# SIDEPANELV5.net
KiCad netlist of a schematic drawn in EAGLE
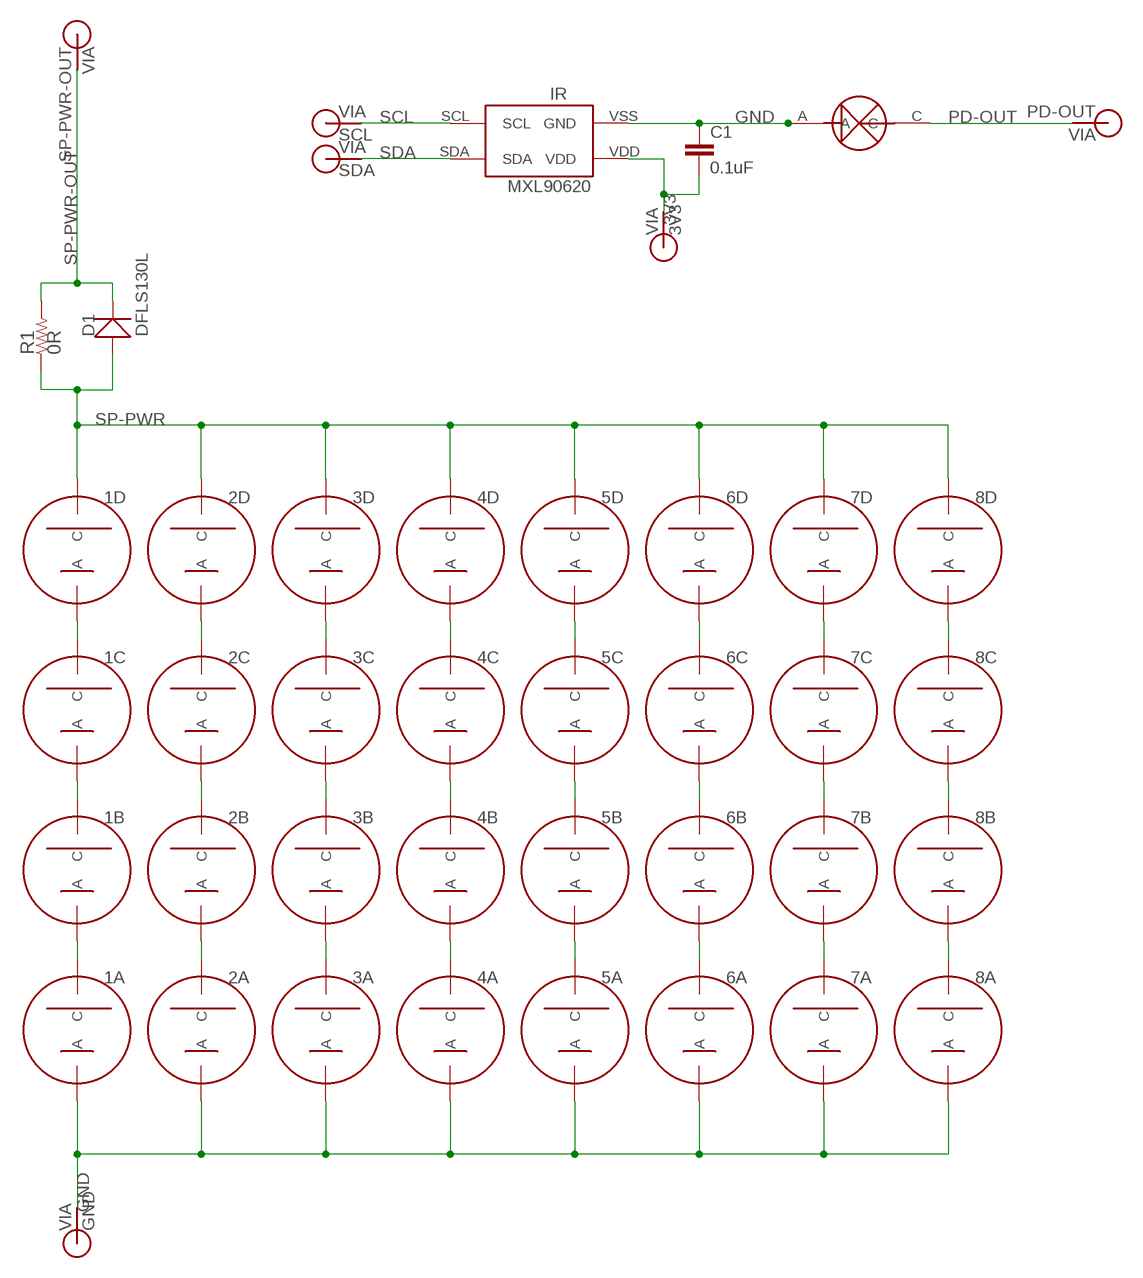
[diagram p0: schematic, sheet 1]

(export (version "E")
  (design (tool "Eeschema 10.0.6"))
  (components
    (comp (ref "1A")
      (value "SOLARCELLV3")
      (footprint "eagle-import:TRISOLX-V3")
      (libsource (lib "eagle-import") (part "SOLARCELLV3"))
    )
    (comp (ref "1B")
      (value "SOLARCELLV3")
      (footprint "eagle-import:TRISOLX-V3")
      (libsource (lib "eagle-import") (part "SOLARCELLV3"))
    )
    (comp (ref "1C")
      (value "SOLARCELLV3")
      (footprint "eagle-import:TRISOLX-V3")
      (libsource (lib "eagle-import") (part "SOLARCELLV3"))
    )
    (comp (ref "1D")
      (value "SOLARCELLV3")
      (footprint "eagle-import:TRISOLX-V3")
      (libsource (lib "eagle-import") (part "SOLARCELLV3"))
    )
    (comp (ref "2A")
      (value "SOLARCELLV3")
      (footprint "eagle-import:TRISOLX-V3")
      (libsource (lib "eagle-import") (part "SOLARCELLV3"))
    )
    (comp (ref "2B")
      (value "SOLARCELLV3")
      (footprint "eagle-import:TRISOLX-V3")
      (libsource (lib "eagle-import") (part "SOLARCELLV3"))
    )
    (comp (ref "2C")
      (value "SOLARCELLV3")
      (footprint "eagle-import:TRISOLX-V3")
      (libsource (lib "eagle-import") (part "SOLARCELLV3"))
    )
    (comp (ref "2D")
      (value "SOLARCELLV3")
      (footprint "eagle-import:TRISOLX-V3")
      (libsource (lib "eagle-import") (part "SOLARCELLV3"))
    )
    (comp (ref "3A")
      (value "SOLARCELLV3")
      (footprint "eagle-import:TRISOLX-V3")
      (libsource (lib "eagle-import") (part "SOLARCELLV3"))
    )
    (comp (ref "3B")
      (value "SOLARCELLV3")
      (footprint "eagle-import:TRISOLX-V3")
      (libsource (lib "eagle-import") (part "SOLARCELLV3"))
    )
    (comp (ref "3C")
      (value "SOLARCELLV3")
      (footprint "eagle-import:TRISOLX-V3")
      (libsource (lib "eagle-import") (part "SOLARCELLV3"))
    )
    (comp (ref "3D")
      (value "SOLARCELLV3")
      (footprint "eagle-import:TRISOLX-V3")
      (libsource (lib "eagle-import") (part "SOLARCELLV3"))
    )
    (comp (ref "3V3")
      (value "3V3")
      (footprint "eagle-import:VIA-60MIL")
      (libsource (lib "eagle-import") (part "VIA-60MIL"))
    )
    (comp (ref "4A")
      (value "SOLARCELLV3")
      (footprint "eagle-import:TRISOLX-V3")
      (libsource (lib "eagle-import") (part "SOLARCELLV3"))
    )
    (comp (ref "4B")
      (value "SOLARCELLV3")
      (footprint "eagle-import:TRISOLX-V3")
      (libsource (lib "eagle-import") (part "SOLARCELLV3"))
    )
    (comp (ref "4C")
      (value "SOLARCELLV3")
      (footprint "eagle-import:TRISOLX-V3")
      (libsource (lib "eagle-import") (part "SOLARCELLV3"))
    )
    (comp (ref "4D")
      (value "SOLARCELLV3")
      (footprint "eagle-import:TRISOLX-V3")
      (libsource (lib "eagle-import") (part "SOLARCELLV3"))
    )
    (comp (ref "5A")
      (value "SOLARCELLV3")
      (footprint "eagle-import:TRISOLX-V3")
      (libsource (lib "eagle-import") (part "SOLARCELLV3"))
    )
    (comp (ref "5B")
      (value "SOLARCELLV3")
      (footprint "eagle-import:TRISOLX-V3")
      (libsource (lib "eagle-import") (part "SOLARCELLV3"))
    )
    (comp (ref "5C")
      (value "SOLARCELLV3")
      (footprint "eagle-import:TRISOLX-V3")
      (libsource (lib "eagle-import") (part "SOLARCELLV3"))
    )
    (comp (ref "5D")
      (value "SOLARCELLV3")
      (footprint "eagle-import:TRISOLX-V3")
      (libsource (lib "eagle-import") (part "SOLARCELLV3"))
    )
    (comp (ref "6A")
      (value "SOLARCELLV3")
      (footprint "eagle-import:TRISOLX-V3")
      (libsource (lib "eagle-import") (part "SOLARCELLV3"))
    )
    (comp (ref "6B")
      (value "SOLARCELLV3")
      (footprint "eagle-import:TRISOLX-V3")
      (libsource (lib "eagle-import") (part "SOLARCELLV3"))
    )
    (comp (ref "6C")
      (value "SOLARCELLV3")
      (footprint "eagle-import:TRISOLX-V3")
      (libsource (lib "eagle-import") (part "SOLARCELLV3"))
    )
    (comp (ref "6D")
      (value "SOLARCELLV3")
      (footprint "eagle-import:TRISOLX-V3")
      (libsource (lib "eagle-import") (part "SOLARCELLV3"))
    )
    (comp (ref "7A")
      (value "SOLARCELLV3")
      (footprint "eagle-import:TRISOLX-V3")
      (libsource (lib "eagle-import") (part "SOLARCELLV3"))
    )
    (comp (ref "7B")
      (value "SOLARCELLV3")
      (footprint "eagle-import:TRISOLX-V3")
      (libsource (lib "eagle-import") (part "SOLARCELLV3"))
    )
    (comp (ref "7C")
      (value "SOLARCELLV3")
      (footprint "eagle-import:TRISOLX-V3")
      (libsource (lib "eagle-import") (part "SOLARCELLV3"))
    )
    (comp (ref "7D")
      (value "SOLARCELLV3")
      (footprint "eagle-import:TRISOLX-V3")
      (libsource (lib "eagle-import") (part "SOLARCELLV3"))
    )
    (comp (ref "8A")
      (value "SOLARCELLV3")
      (footprint "eagle-import:TRISOLX-V3")
      (libsource (lib "eagle-import") (part "SOLARCELLV3"))
    )
    (comp (ref "8B")
      (value "SOLARCELLV3")
      (footprint "eagle-import:TRISOLX-V3")
      (libsource (lib "eagle-import") (part "SOLARCELLV3"))
    )
    (comp (ref "8C")
      (value "SOLARCELLV3")
      (footprint "eagle-import:TRISOLX-V3")
      (libsource (lib "eagle-import") (part "SOLARCELLV3"))
    )
    (comp (ref "8D")
      (value "SOLARCELLV3")
      (footprint "eagle-import:TRISOLX-V3")
      (libsource (lib "eagle-import") (part "SOLARCELLV3"))
    )
    (comp (ref "C1")
      (value "0.1uF")
      (footprint "eagle-import:0805")
      (libsource (lib "eagle-import") (part "CAP0805"))
    )
    (comp (ref "D1")
      (value "DFLS130L")
      (footprint "eagle-import:PWRDI-123")
      (libsource (lib "eagle-import") (part "DFLS130L"))
    )
    (comp (ref "GND")
      (value "GND")
      (footprint "eagle-import:VIA-60MIL")
      (libsource (lib "eagle-import") (part "VIA-60MIL"))
    )
    (comp (ref "IR")
      (value "MXL90620")
      (footprint "eagle-import:MXL90620")
      (libsource (lib "eagle-import") (part "MXL90620"))
    )
    (comp (ref "PD")
      (value "PHOTODETECTOR")
      (footprint "eagle-import:PHOTODECTORDEVICE2")
      (libsource (lib "eagle-import") (part "PHOTODETECTOR"))
    )
    (comp (ref "PD-OUT")
      (value "PD-OUT")
      (footprint "eagle-import:VIA-60MIL")
      (libsource (lib "eagle-import") (part "VIA-60MIL"))
    )
    (comp (ref "PWR-OUT")
      (value "SP-PWR-OUT")
      (footprint "eagle-import:VIA-60MIL")
      (libsource (lib "eagle-import") (part "VIA-60MIL"))
    )
    (comp (ref "R1")
      (value "0R")
      (footprint "eagle-import:1210")
      (libsource (lib "eagle-import") (part "RES1210"))
    )
    (comp (ref "SCL")
      (value "SCL")
      (footprint "eagle-import:VIA-60MIL")
      (libsource (lib "eagle-import") (part "VIA-60MIL"))
    )
    (comp (ref "SDA")
      (value "SDA")
      (footprint "eagle-import:VIA-60MIL")
      (libsource (lib "eagle-import") (part "VIA-60MIL"))
    )
  )
  (nets
    (net (code "1") (name "/3V3") (class "Default")
      (node (ref "3V3") (pin "P$1") (pinfunction "P$1_P$1") (pintype "bidirectional"))
      (node (ref "C1") (pin "2") (pinfunction "2_2") (pintype "passive"))
      (node (ref "IR") (pin "VDD") (pinfunction "VDD_VDD") (pintype "bidirectional"))
    )
    (net (code "2") (name "/GND") (class "Default")
      (node (ref "1A") (pin "ANODE") (pinfunction "A_ANODE") (pintype "bidirectional"))
      (node (ref "2A") (pin "ANODE") (pinfunction "A_ANODE") (pintype "bidirectional"))
      (node (ref "3A") (pin "ANODE") (pinfunction "A_ANODE") (pintype "bidirectional"))
      (node (ref "4A") (pin "ANODE") (pinfunction "A_ANODE") (pintype "bidirectional"))
      (node (ref "5A") (pin "ANODE") (pinfunction "A_ANODE") (pintype "bidirectional"))
      (node (ref "6A") (pin "ANODE") (pinfunction "A_ANODE") (pintype "bidirectional"))
      (node (ref "7A") (pin "ANODE") (pinfunction "A_ANODE") (pintype "bidirectional"))
      (node (ref "8A") (pin "ANODE") (pinfunction "A_ANODE") (pintype "bidirectional"))
      (node (ref "C1") (pin "1") (pinfunction "1_1") (pintype "passive"))
      (node (ref "GND") (pin "P$1") (pinfunction "P$1_P$1") (pintype "bidirectional"))
      (node (ref "IR") (pin "VSS") (pinfunction "GND_VSS") (pintype "bidirectional"))
      (node (ref "PD") (pin "A") (pinfunction "A_A") (pintype "bidirectional"))
    )
    (net (code "3") (name "/PD-OUT") (class "Default")
      (node (ref "PD") (pin "C") (pinfunction "C_C") (pintype "bidirectional"))
      (node (ref "PD-OUT") (pin "P$1") (pinfunction "P$1_P$1") (pintype "bidirectional"))
    )
    (net (code "4") (name "/SCL") (class "Default")
      (node (ref "IR") (pin "SCL") (pinfunction "SCL_SCL") (pintype "bidirectional"))
      (node (ref "SCL") (pin "P$1") (pinfunction "P$1_P$1") (pintype "bidirectional"))
    )
    (net (code "5") (name "/SDA") (class "Default")
      (node (ref "IR") (pin "SDA") (pinfunction "SDA_SDA") (pintype "bidirectional"))
      (node (ref "SDA") (pin "P$1") (pinfunction "P$1_P$1") (pintype "bidirectional"))
    )
    (net (code "6") (name "/SP-PWR") (class "Default")
      (node (ref "1D") (pin "CATHODE") (pinfunction "C_CATHODE") (pintype "bidirectional"))
      (node (ref "2D") (pin "CATHODE") (pinfunction "C_CATHODE") (pintype "bidirectional"))
      (node (ref "3D") (pin "CATHODE") (pinfunction "C_CATHODE") (pintype "bidirectional"))
      (node (ref "4D") (pin "CATHODE") (pinfunction "C_CATHODE") (pintype "bidirectional"))
      (node (ref "5D") (pin "CATHODE") (pinfunction "C_CATHODE") (pintype "bidirectional"))
      (node (ref "6D") (pin "CATHODE") (pinfunction "C_CATHODE") (pintype "bidirectional"))
      (node (ref "7D") (pin "CATHODE") (pinfunction "C_CATHODE") (pintype "bidirectional"))
      (node (ref "8D") (pin "CATHODE") (pinfunction "C_CATHODE") (pintype "bidirectional"))
      (node (ref "D1") (pin "A") (pinfunction "A_A") (pintype "bidirectional"))
      (node (ref "R1") (pin "P$1") (pinfunction "1_P$1") (pintype "passive"))
    )
    (net (code "7") (name "/SP-PWR-OUT") (class "Default")
      (node (ref "D1") (pin "C") (pinfunction "C_C") (pintype "bidirectional"))
      (node (ref "PWR-OUT") (pin "P$1") (pinfunction "P$1_P$1") (pintype "bidirectional"))
      (node (ref "R1") (pin "P$2") (pinfunction "2_P$2") (pintype "passive"))
    )
    (net (code "8") (name "Net-(1A-C)") (class "Default")
      (node (ref "1A") (pin "CATHODE") (pinfunction "C_CATHODE") (pintype "bidirectional"))
      (node (ref "1B") (pin "ANODE") (pinfunction "A_ANODE") (pintype "bidirectional"))
    )
    (net (code "9") (name "Net-(1B-C)") (class "Default")
      (node (ref "1B") (pin "CATHODE") (pinfunction "C_CATHODE") (pintype "bidirectional"))
      (node (ref "1C") (pin "ANODE") (pinfunction "A_ANODE") (pintype "bidirectional"))
    )
    (net (code "10") (name "Net-(1C-C)") (class "Default")
      (node (ref "1C") (pin "CATHODE") (pinfunction "C_CATHODE") (pintype "bidirectional"))
      (node (ref "1D") (pin "ANODE") (pinfunction "A_ANODE") (pintype "bidirectional"))
    )
    (net (code "11") (name "Net-(2A-C)") (class "Default")
      (node (ref "2A") (pin "CATHODE") (pinfunction "C_CATHODE") (pintype "bidirectional"))
      (node (ref "2B") (pin "ANODE") (pinfunction "A_ANODE") (pintype "bidirectional"))
    )
    (net (code "12") (name "Net-(2B-C)") (class "Default")
      (node (ref "2B") (pin "CATHODE") (pinfunction "C_CATHODE") (pintype "bidirectional"))
      (node (ref "2C") (pin "ANODE") (pinfunction "A_ANODE") (pintype "bidirectional"))
    )
    (net (code "13") (name "Net-(2C-C)") (class "Default")
      (node (ref "2C") (pin "CATHODE") (pinfunction "C_CATHODE") (pintype "bidirectional"))
      (node (ref "2D") (pin "ANODE") (pinfunction "A_ANODE") (pintype "bidirectional"))
    )
    (net (code "14") (name "Net-(3A-C)") (class "Default")
      (node (ref "3A") (pin "CATHODE") (pinfunction "C_CATHODE") (pintype "bidirectional"))
      (node (ref "3B") (pin "ANODE") (pinfunction "A_ANODE") (pintype "bidirectional"))
    )
    (net (code "15") (name "Net-(3B-C)") (class "Default")
      (node (ref "3B") (pin "CATHODE") (pinfunction "C_CATHODE") (pintype "bidirectional"))
      (node (ref "3C") (pin "ANODE") (pinfunction "A_ANODE") (pintype "bidirectional"))
    )
    (net (code "16") (name "Net-(3C-C)") (class "Default")
      (node (ref "3C") (pin "CATHODE") (pinfunction "C_CATHODE") (pintype "bidirectional"))
      (node (ref "3D") (pin "ANODE") (pinfunction "A_ANODE") (pintype "bidirectional"))
    )
    (net (code "17") (name "Net-(4A-C)") (class "Default")
      (node (ref "4A") (pin "CATHODE") (pinfunction "C_CATHODE") (pintype "bidirectional"))
      (node (ref "4B") (pin "ANODE") (pinfunction "A_ANODE") (pintype "bidirectional"))
    )
    (net (code "18") (name "Net-(4B-C)") (class "Default")
      (node (ref "4B") (pin "CATHODE") (pinfunction "C_CATHODE") (pintype "bidirectional"))
      (node (ref "4C") (pin "ANODE") (pinfunction "A_ANODE") (pintype "bidirectional"))
    )
    (net (code "19") (name "Net-(4C-C)") (class "Default")
      (node (ref "4C") (pin "CATHODE") (pinfunction "C_CATHODE") (pintype "bidirectional"))
      (node (ref "4D") (pin "ANODE") (pinfunction "A_ANODE") (pintype "bidirectional"))
    )
    (net (code "20") (name "Net-(5A-C)") (class "Default")
      (node (ref "5A") (pin "CATHODE") (pinfunction "C_CATHODE") (pintype "bidirectional"))
      (node (ref "5B") (pin "ANODE") (pinfunction "A_ANODE") (pintype "bidirectional"))
    )
    (net (code "21") (name "Net-(5B-C)") (class "Default")
      (node (ref "5B") (pin "CATHODE") (pinfunction "C_CATHODE") (pintype "bidirectional"))
      (node (ref "5C") (pin "ANODE") (pinfunction "A_ANODE") (pintype "bidirectional"))
    )
    (net (code "22") (name "Net-(5C-C)") (class "Default")
      (node (ref "5C") (pin "CATHODE") (pinfunction "C_CATHODE") (pintype "bidirectional"))
      (node (ref "5D") (pin "ANODE") (pinfunction "A_ANODE") (pintype "bidirectional"))
    )
    (net (code "23") (name "Net-(6A-C)") (class "Default")
      (node (ref "6A") (pin "CATHODE") (pinfunction "C_CATHODE") (pintype "bidirectional"))
      (node (ref "6B") (pin "ANODE") (pinfunction "A_ANODE") (pintype "bidirectional"))
    )
    (net (code "24") (name "Net-(6B-C)") (class "Default")
      (node (ref "6B") (pin "CATHODE") (pinfunction "C_CATHODE") (pintype "bidirectional"))
      (node (ref "6C") (pin "ANODE") (pinfunction "A_ANODE") (pintype "bidirectional"))
    )
    (net (code "25") (name "Net-(6C-C)") (class "Default")
      (node (ref "6C") (pin "CATHODE") (pinfunction "C_CATHODE") (pintype "bidirectional"))
      (node (ref "6D") (pin "ANODE") (pinfunction "A_ANODE") (pintype "bidirectional"))
    )
    (net (code "26") (name "Net-(7A-C)") (class "Default")
      (node (ref "7A") (pin "CATHODE") (pinfunction "C_CATHODE") (pintype "bidirectional"))
      (node (ref "7B") (pin "ANODE") (pinfunction "A_ANODE") (pintype "bidirectional"))
    )
    (net (code "27") (name "Net-(7B-C)") (class "Default")
      (node (ref "7B") (pin "CATHODE") (pinfunction "C_CATHODE") (pintype "bidirectional"))
      (node (ref "7C") (pin "ANODE") (pinfunction "A_ANODE") (pintype "bidirectional"))
    )
    (net (code "28") (name "Net-(7C-C)") (class "Default")
      (node (ref "7C") (pin "CATHODE") (pinfunction "C_CATHODE") (pintype "bidirectional"))
      (node (ref "7D") (pin "ANODE") (pinfunction "A_ANODE") (pintype "bidirectional"))
    )
    (net (code "29") (name "Net-(8A-C)") (class "Default")
      (node (ref "8A") (pin "CATHODE") (pinfunction "C_CATHODE") (pintype "bidirectional"))
      (node (ref "8B") (pin "ANODE") (pinfunction "A_ANODE") (pintype "bidirectional"))
    )
    (net (code "30") (name "Net-(8B-C)") (class "Default")
      (node (ref "8B") (pin "CATHODE") (pinfunction "C_CATHODE") (pintype "bidirectional"))
      (node (ref "8C") (pin "ANODE") (pinfunction "A_ANODE") (pintype "bidirectional"))
    )
    (net (code "31") (name "Net-(8C-C)") (class "Default")
      (node (ref "8C") (pin "CATHODE") (pinfunction "C_CATHODE") (pintype "bidirectional"))
      (node (ref "8D") (pin "ANODE") (pinfunction "A_ANODE") (pintype "bidirectional"))
    )
  )
)
